# ARP_Odyssey_VCO_1_3.net
KiCad netlist of a schematic drawn in EAGLE
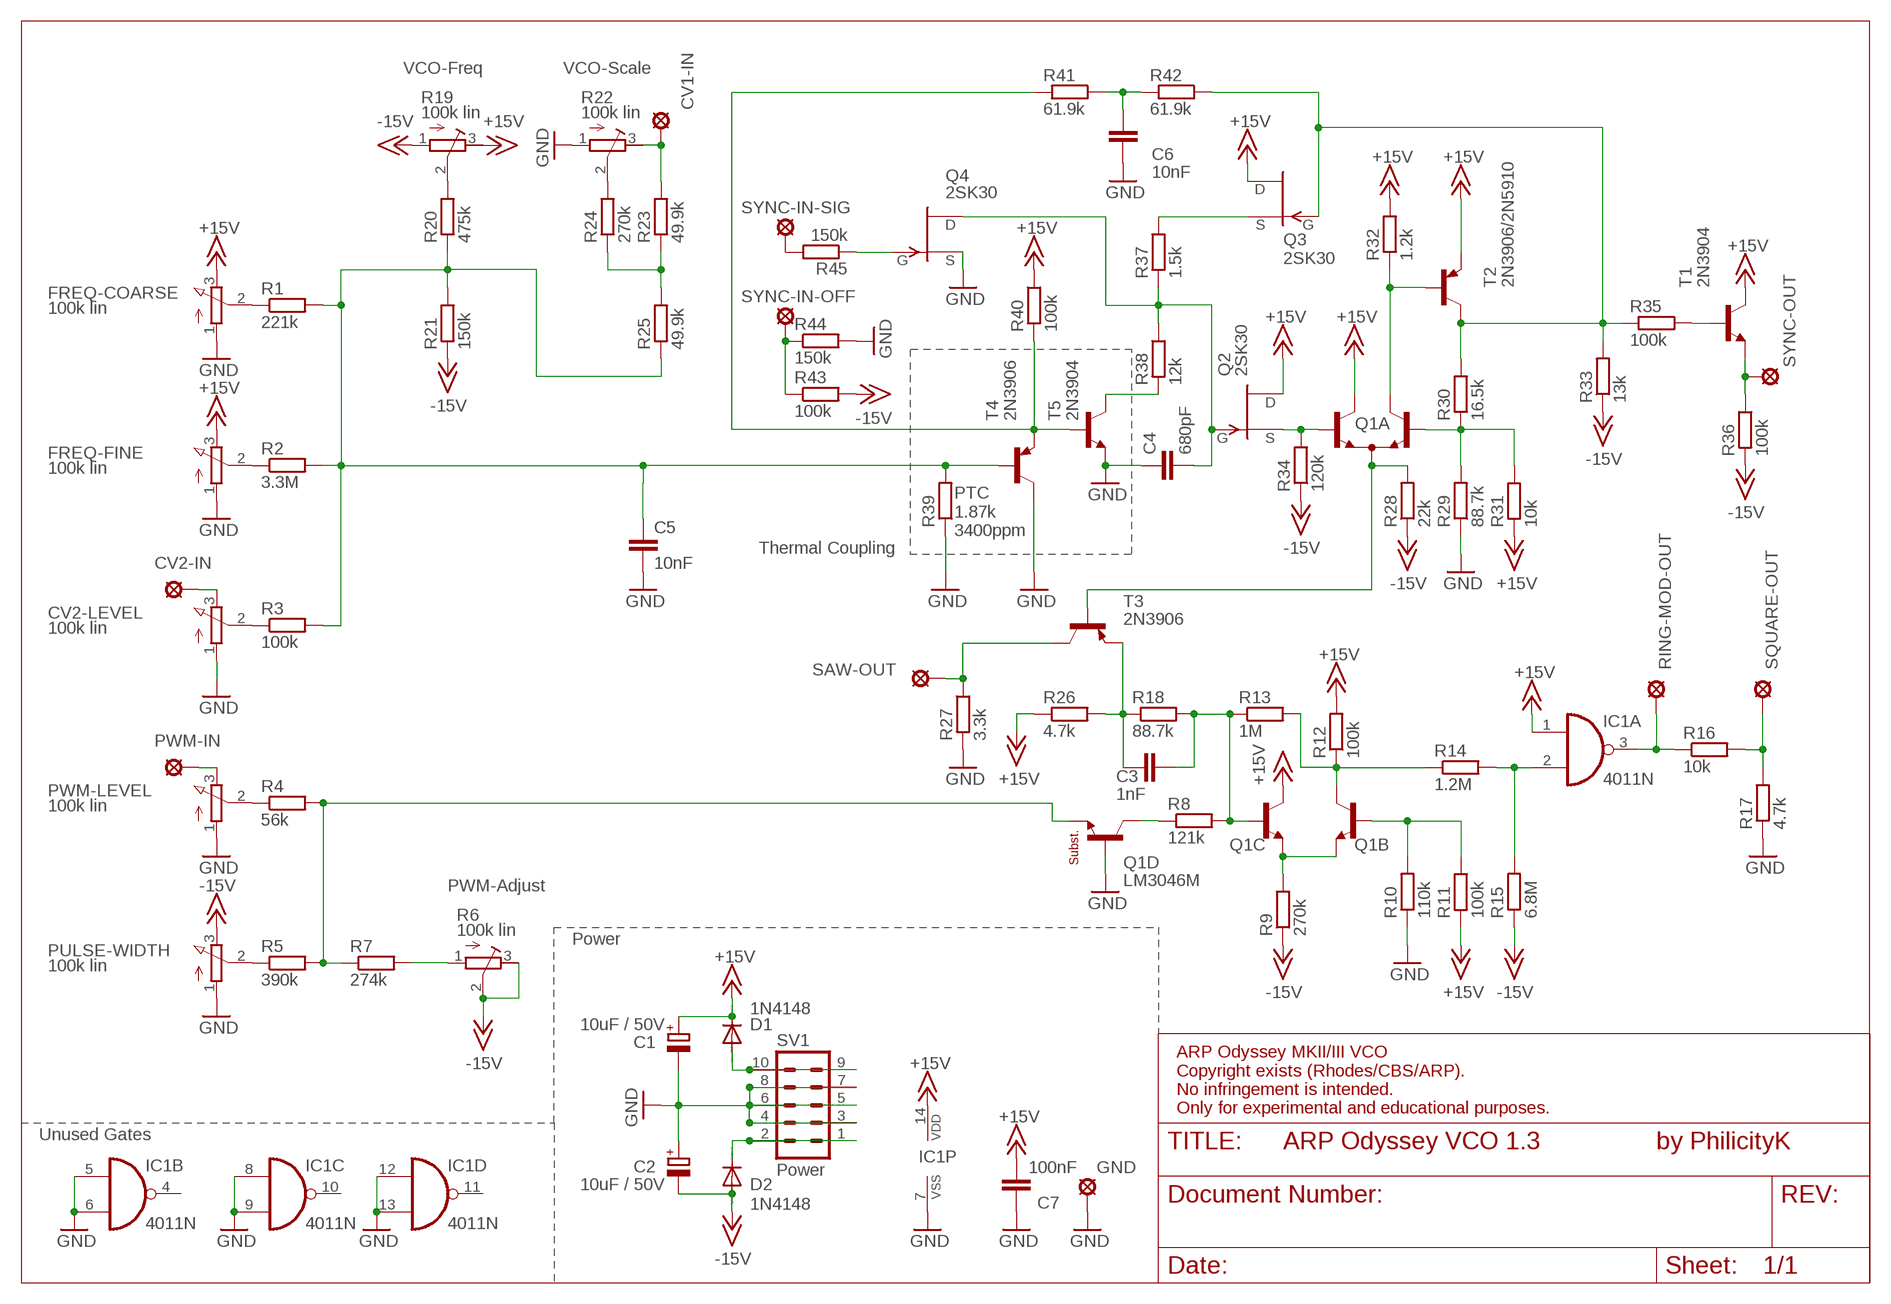
[diagram p0: schematic, sheet 1]

(export (version "E")
  (design (tool "Eeschema 10.0.6"))
  (components
    (comp (ref "C1")
      (value "10uF / 50V")
      (footprint "eagle-import:E2,5-6E")
      (libsource (lib "eagle-import") (part "CPOL-EUE2,5-6E"))
    )
    (comp (ref "C2")
      (value "10uF / 50V")
      (footprint "eagle-import:E2,5-6E")
      (libsource (lib "eagle-import") (part "CPOL-EUE2,5-6E"))
    )
    (comp (ref "C3")
      (value "1nF")
      (footprint "eagle-import:C050-045X075")
      (libsource (lib "eagle-import") (part "C-EU050-045X075"))
    )
    (comp (ref "C4")
      (value "680pF")
      (footprint "eagle-import:C050-045X075")
      (libsource (lib "eagle-import") (part "C-EU050-045X075"))
    )
    (comp (ref "C5")
      (value "10nF")
      (footprint "eagle-import:C050-045X075")
      (libsource (lib "eagle-import") (part "C-EU050-045X075"))
    )
    (comp (ref "C6")
      (value "10nF")
      (footprint "eagle-import:C050-045X075")
      (libsource (lib "eagle-import") (part "C-EU050-045X075"))
    )
    (comp (ref "C7")
      (value "100nF")
      (footprint "eagle-import:C050-045X075")
      (libsource (lib "eagle-import") (part "C-EU050-045X075"))
    )
    (comp (ref "CV1-IN")
      (value "SE11")
      (footprint "eagle-import:SE11")
      (libsource (lib "eagle-import") (part "SE11"))
    )
    (comp (ref "CV2-IN")
      (value "SE11")
      (footprint "eagle-import:SE11")
      (libsource (lib "eagle-import") (part "SE11"))
    )
    (comp (ref "CV2-LEVEL")
      (value "100k lin")
      (footprint "eagle-import:RK11K112")
      (libsource (lib "eagle-import") (part "RK11K112"))
    )
    (comp (ref "D1")
      (value "1N4148")
      (footprint "eagle-import:DO35-7")
      (libsource (lib "eagle-import") (part "1N4148DO35-7"))
    )
    (comp (ref "D2")
      (value "1N4148")
      (footprint "eagle-import:DO35-7")
      (libsource (lib "eagle-import") (part "1N4148DO35-7"))
    )
    (comp (ref "FREQ-COARSE")
      (value "100k lin")
      (footprint "eagle-import:RK11K112")
      (libsource (lib "eagle-import") (part "RK11K112"))
    )
    (comp (ref "FREQ-FINE")
      (value "100k lin")
      (footprint "eagle-import:RK11K112")
      (libsource (lib "eagle-import") (part "RK11K112"))
    )
    (comp (ref "GND")
      (value "SE11")
      (footprint "eagle-import:SE11")
      (libsource (lib "eagle-import") (part "SE11"))
    )
    (comp (ref "IC1")
      (value "4011N")
      (footprint "eagle-import:DIL14")
      (libsource (lib "eagle-import") (part "4011N"))
    )
    (comp (ref "PULSE-WIDTH")
      (value "100k lin")
      (footprint "eagle-import:RK11K112")
      (libsource (lib "eagle-import") (part "RK11K112"))
    )
    (comp (ref "PWM-IN")
      (value "SE11")
      (footprint "eagle-import:SE11")
      (libsource (lib "eagle-import") (part "SE11"))
    )
    (comp (ref "PWM-LEVEL")
      (value "100k lin")
      (footprint "eagle-import:RK11K112")
      (libsource (lib "eagle-import") (part "RK11K112"))
    )
    (comp (ref "Q1")
      (value "LM3046M")
      (footprint "eagle-import:SO14")
      (libsource (lib "eagle-import") (part "LM3046M/NOPB"))
    )
    (comp (ref "Q2")
      (value "2SK30")
      (footprint "eagle-import:TO92")
      (libsource (lib "eagle-import") (part "2SK30"))
    )
    (comp (ref "Q3")
      (value "2SK30")
      (footprint "eagle-import:TO92")
      (libsource (lib "eagle-import") (part "2SK30"))
    )
    (comp (ref "Q4")
      (value "2SK30")
      (footprint "eagle-import:TO92")
      (libsource (lib "eagle-import") (part "2SK30"))
    )
    (comp (ref "R1")
      (value "221k")
      (footprint "eagle-import:0207_7")
      (libsource (lib "eagle-import") (part "R-EU_0207/7"))
    )
    (comp (ref "R2")
      (value "3.3M")
      (footprint "eagle-import:0207_7")
      (libsource (lib "eagle-import") (part "R-EU_0207/7"))
    )
    (comp (ref "R3")
      (value "100k")
      (footprint "eagle-import:0207_7")
      (libsource (lib "eagle-import") (part "R-EU_0207/7"))
    )
    (comp (ref "R4")
      (value "56k")
      (footprint "eagle-import:0207_7")
      (libsource (lib "eagle-import") (part "R-EU_0207/7"))
    )
    (comp (ref "R5")
      (value "390k")
      (footprint "eagle-import:0207_7")
      (libsource (lib "eagle-import") (part "R-EU_0207/7"))
    )
    (comp (ref "R6")
      (value "100k lin")
      (footprint "eagle-import:RTRIM64W")
      (libsource (lib "eagle-import") (part "R-TRIMM64W"))
    )
    (comp (ref "R7")
      (value "274k")
      (footprint "eagle-import:0207_7")
      (libsource (lib "eagle-import") (part "R-EU_0207/7"))
    )
    (comp (ref "R8")
      (value "121k")
      (footprint "eagle-import:0207_7")
      (libsource (lib "eagle-import") (part "R-EU_0207/7"))
    )
    (comp (ref "R9")
      (value "270k")
      (footprint "eagle-import:0207_7")
      (libsource (lib "eagle-import") (part "R-EU_0207/7"))
    )
    (comp (ref "R10")
      (value "110k")
      (footprint "eagle-import:0207_7")
      (libsource (lib "eagle-import") (part "R-EU_0207/7"))
    )
    (comp (ref "R11")
      (value "100k")
      (footprint "eagle-import:0207_7")
      (libsource (lib "eagle-import") (part "R-EU_0207/7"))
    )
    (comp (ref "R12")
      (value "100k")
      (footprint "eagle-import:0207_7")
      (libsource (lib "eagle-import") (part "R-EU_0207/7"))
    )
    (comp (ref "R13")
      (value "1M")
      (footprint "eagle-import:0207_7")
      (libsource (lib "eagle-import") (part "R-EU_0207/7"))
    )
    (comp (ref "R14")
      (value "1.2M")
      (footprint "eagle-import:0207_7")
      (libsource (lib "eagle-import") (part "R-EU_0207/7"))
    )
    (comp (ref "R15")
      (value "6.8M")
      (footprint "eagle-import:0207_7")
      (libsource (lib "eagle-import") (part "R-EU_0207/7"))
    )
    (comp (ref "R16")
      (value "10k")
      (footprint "eagle-import:0207_7")
      (libsource (lib "eagle-import") (part "R-EU_0207/7"))
    )
    (comp (ref "R17")
      (value "4.7k")
      (footprint "eagle-import:0207_7")
      (libsource (lib "eagle-import") (part "R-EU_0207/7"))
    )
    (comp (ref "R18")
      (value "88.7k")
      (footprint "eagle-import:0207_7")
      (libsource (lib "eagle-import") (part "R-EU_0207/7"))
    )
    (comp (ref "R19")
      (value "100k lin")
      (footprint "eagle-import:RTRIM64W")
      (libsource (lib "eagle-import") (part "R-TRIMM64W"))
    )
    (comp (ref "R20")
      (value "475k")
      (footprint "eagle-import:0207_7")
      (libsource (lib "eagle-import") (part "R-EU_0207/7"))
    )
    (comp (ref "R21")
      (value "150k")
      (footprint "eagle-import:0207_7")
      (libsource (lib "eagle-import") (part "R-EU_0207/7"))
    )
    (comp (ref "R22")
      (value "100k lin")
      (footprint "eagle-import:RTRIM64W")
      (libsource (lib "eagle-import") (part "R-TRIMM64W"))
    )
    (comp (ref "R23")
      (value "49.9k")
      (footprint "eagle-import:0207_7")
      (libsource (lib "eagle-import") (part "R-EU_0207/7"))
    )
    (comp (ref "R24")
      (value "270k")
      (footprint "eagle-import:0207_7")
      (libsource (lib "eagle-import") (part "R-EU_0207/7"))
    )
    (comp (ref "R25")
      (value "49.9k")
      (footprint "eagle-import:0207_7")
      (libsource (lib "eagle-import") (part "R-EU_0207/7"))
    )
    (comp (ref "R26")
      (value "4.7k")
      (footprint "eagle-import:0207_7")
      (libsource (lib "eagle-import") (part "R-EU_0207/7"))
    )
    (comp (ref "R27")
      (value "3.3k")
      (footprint "eagle-import:0207_7")
      (libsource (lib "eagle-import") (part "R-EU_0207/7"))
    )
    (comp (ref "R28")
      (value "22k")
      (footprint "eagle-import:0207_7")
      (libsource (lib "eagle-import") (part "R-EU_0207/7"))
    )
    (comp (ref "R29")
      (value "88.7k")
      (footprint "eagle-import:0207_7")
      (libsource (lib "eagle-import") (part "R-EU_0207/7"))
    )
    (comp (ref "R30")
      (value "16.5k")
      (footprint "eagle-import:0207_7")
      (libsource (lib "eagle-import") (part "R-EU_0207/7"))
    )
    (comp (ref "R31")
      (value "10k")
      (footprint "eagle-import:0207_7")
      (libsource (lib "eagle-import") (part "R-EU_0207/7"))
    )
    (comp (ref "R32")
      (value "1.2k")
      (footprint "eagle-import:0207_7")
      (libsource (lib "eagle-import") (part "R-EU_0207/7"))
    )
    (comp (ref "R33")
      (value "13k")
      (footprint "eagle-import:0207_7")
      (libsource (lib "eagle-import") (part "R-EU_0207/7"))
    )
    (comp (ref "R34")
      (value "120k")
      (footprint "eagle-import:0207_7")
      (libsource (lib "eagle-import") (part "R-EU_0207/7"))
    )
    (comp (ref "R35")
      (value "100k")
      (footprint "eagle-import:0207_7")
      (libsource (lib "eagle-import") (part "R-EU_0207/7"))
    )
    (comp (ref "R36")
      (value "100k")
      (footprint "eagle-import:0207_7")
      (libsource (lib "eagle-import") (part "R-EU_0207/7"))
    )
    (comp (ref "R37")
      (value "1.5k")
      (footprint "eagle-import:0207_7")
      (libsource (lib "eagle-import") (part "R-EU_0207/7"))
    )
    (comp (ref "R38")
      (value "12k")
      (footprint "eagle-import:0207_7")
      (libsource (lib "eagle-import") (part "R-EU_0207/7"))
    )
    (comp (ref "R39")
      (value "PTC 1.87k")
      (footprint "eagle-import:0207_7")
      (libsource (lib "eagle-import") (part "R-EU_0207/7"))
    )
    (comp (ref "R40")
      (value "100k")
      (footprint "eagle-import:0207_7")
      (libsource (lib "eagle-import") (part "R-EU_0207/7"))
    )
    (comp (ref "R41")
      (value "61.9k")
      (footprint "eagle-import:0207_7")
      (libsource (lib "eagle-import") (part "R-EU_0207/7"))
    )
    (comp (ref "R42")
      (value "61.9k")
      (footprint "eagle-import:0207_7")
      (libsource (lib "eagle-import") (part "R-EU_0207/7"))
    )
    (comp (ref "R43")
      (value "100k")
      (footprint "eagle-import:0207_7")
      (libsource (lib "eagle-import") (part "R-EU_0207/7"))
    )
    (comp (ref "R44")
      (value "150k")
      (footprint "eagle-import:0207_7")
      (libsource (lib "eagle-import") (part "R-EU_0207/7"))
    )
    (comp (ref "R45")
      (value "150k")
      (footprint "eagle-import:0207_7")
      (libsource (lib "eagle-import") (part "R-EU_0207/7"))
    )
    (comp (ref "RING-MOD-OUT")
      (value "SE11")
      (footprint "eagle-import:SE11")
      (libsource (lib "eagle-import") (part "SE11"))
    )
    (comp (ref "SAW-OUT")
      (value "SE11")
      (footprint "eagle-import:SE11")
      (libsource (lib "eagle-import") (part "SE11"))
    )
    (comp (ref "SQUARE-OUT")
      (value "SE11")
      (footprint "eagle-import:SE11")
      (libsource (lib "eagle-import") (part "SE11"))
    )
    (comp (ref "SV1")
      (value "Power")
      (footprint "eagle-import:ML10")
      (libsource (lib "eagle-import") (part "ML10"))
    )
    (comp (ref "SYNC-IN-OFF")
      (value "SE11")
      (footprint "eagle-import:SE11")
      (libsource (lib "eagle-import") (part "SE11"))
    )
    (comp (ref "SYNC-IN-SIG")
      (value "SE11")
      (footprint "eagle-import:SE11")
      (libsource (lib "eagle-import") (part "SE11"))
    )
    (comp (ref "SYNC-OUT")
      (value "SE11")
      (footprint "eagle-import:SE11")
      (libsource (lib "eagle-import") (part "SE11"))
    )
    (comp (ref "T1")
      (value "2N3904")
      (footprint "eagle-import:TO92-EBC")
      (libsource (lib "eagle-import") (part "-NPN-TO92-EBC2N3904"))
    )
    (comp (ref "T2")
      (value "2N3906/2N5910")
      (footprint "eagle-import:TO92-EBC")
      (libsource (lib "eagle-import") (part "-PNP-TO92-EBC2N3906"))
    )
    (comp (ref "T3")
      (value "2N3906")
      (footprint "eagle-import:TO92-EBC")
      (libsource (lib "eagle-import") (part "-PNP-TO92-EBC2N3906"))
    )
    (comp (ref "T4")
      (value "2N3906")
      (footprint "eagle-import:TO92-EBC")
      (libsource (lib "eagle-import") (part "-PNP-TO92-EBC2N3906"))
    )
    (comp (ref "T5")
      (value "2N3904")
      (footprint "eagle-import:TO92-EBC")
      (libsource (lib "eagle-import") (part "-NPN-TO92-EBC2N3904"))
    )
  )
  (nets
    (net (code "1") (name "+15V") (class "Default")
      (node (ref "C1") (pin "+") (pinfunction "+_+") (pintype "passive"))
      (node (ref "C7") (pin "2") (pinfunction "2_2") (pintype "passive"))
      (node (ref "D1") (pin "C") (pinfunction "C_C") (pintype "passive"))
      (node (ref "FREQ-COARSE") (pin "3") (pinfunction "E_3") (pintype "passive"))
      (node (ref "FREQ-FINE") (pin "3") (pinfunction "E_3") (pintype "passive"))
      (node (ref "IC1") (pin "1") (pinfunction "I0_1") (pintype "input"))
      (node (ref "IC1") (pin "14") (pinfunction "VDD_14") (pintype "power_in"))
      (node (ref "Q1") (pin "11") (pinfunction "C_11") (pintype "passive"))
      (node (ref "Q1") (pin "5") (pinfunction "C2_5") (pintype "passive"))
      (node (ref "Q2") (pin "3") (pinfunction "D_3") (pintype "passive"))
      (node (ref "Q3") (pin "3") (pinfunction "D_3") (pintype "passive"))
      (node (ref "R11") (pin "2") (pinfunction "2_2") (pintype "passive"))
      (node (ref "R12") (pin "2") (pinfunction "2_2") (pintype "passive"))
      (node (ref "R19") (pin "3") (pinfunction "E_3") (pintype "passive"))
      (node (ref "R26") (pin "1") (pinfunction "1_1") (pintype "passive"))
      (node (ref "R31") (pin "2") (pinfunction "2_2") (pintype "passive"))
      (node (ref "R32") (pin "2") (pinfunction "2_2") (pintype "passive"))
      (node (ref "R40") (pin "1") (pinfunction "1_1") (pintype "passive"))
      (node (ref "T1") (pin "C") (pinfunction "C_C") (pintype "passive"))
      (node (ref "T2") (pin "E") (pinfunction "E_E") (pintype "passive"))
    )
    (net (code "2") (name "-15V") (class "Default")
      (node (ref "C2") (pin "-") (pinfunction "-_-") (pintype "passive"))
      (node (ref "D2") (pin "A") (pinfunction "A_A") (pintype "passive"))
      (node (ref "PULSE-WIDTH") (pin "3") (pinfunction "E_3") (pintype "passive"))
      (node (ref "R15") (pin "1") (pinfunction "1_1") (pintype "passive"))
      (node (ref "R19") (pin "1") (pinfunction "A_1") (pintype "passive"))
      (node (ref "R21") (pin "2") (pinfunction "2_2") (pintype "passive"))
      (node (ref "R28") (pin "1") (pinfunction "1_1") (pintype "passive"))
      (node (ref "R33") (pin "1") (pinfunction "1_1") (pintype "passive"))
      (node (ref "R34") (pin "1") (pinfunction "1_1") (pintype "passive"))
      (node (ref "R36") (pin "2") (pinfunction "2_2") (pintype "passive"))
      (node (ref "R43") (pin "2") (pinfunction "2_2") (pintype "passive"))
      (node (ref "R6") (pin "2") (pinfunction "S_2") (pintype "passive"))
      (node (ref "R6") (pin "3") (pinfunction "E_3") (pintype "passive"))
      (node (ref "R9") (pin "1") (pinfunction "1_1") (pintype "passive"))
    )
    (net (code "3") (name "GND") (class "Default")
      (node (ref "C1") (pin "-") (pinfunction "-_-") (pintype "passive"))
      (node (ref "C2") (pin "+") (pinfunction "+_+") (pintype "passive"))
      (node (ref "C4") (pin "1") (pinfunction "1_1") (pintype "passive"))
      (node (ref "C5") (pin "2") (pinfunction "2_2") (pintype "passive"))
      (node (ref "C6") (pin "2") (pinfunction "2_2") (pintype "passive"))
      (node (ref "C7") (pin "1") (pinfunction "1_1") (pintype "passive"))
      (node (ref "CV2-LEVEL") (pin "1") (pinfunction "A_1") (pintype "passive"))
      (node (ref "FREQ-COARSE") (pin "1") (pinfunction "A_1") (pintype "passive"))
      (node (ref "FREQ-FINE") (pin "1") (pinfunction "A_1") (pintype "passive"))
      (node (ref "GND") (pin "MP") (pinfunction "MP_MP") (pintype "passive"))
      (node (ref "IC1") (pin "12") (pinfunction "I0_12") (pintype "input"))
      (node (ref "IC1") (pin "13") (pinfunction "I1_13") (pintype "input"))
      (node (ref "IC1") (pin "5") (pinfunction "I0_5") (pintype "input"))
      (node (ref "IC1") (pin "6") (pinfunction "I1_6") (pintype "input"))
      (node (ref "IC1") (pin "7") (pinfunction "VSS_7") (pintype "power_in"))
      (node (ref "IC1") (pin "8") (pinfunction "I0_8") (pintype "input"))
      (node (ref "IC1") (pin "9") (pinfunction "I1_9") (pintype "input"))
      (node (ref "PULSE-WIDTH") (pin "1") (pinfunction "A_1") (pintype "passive"))
      (node (ref "PWM-LEVEL") (pin "1") (pinfunction "A_1") (pintype "passive"))
      (node (ref "Q1") (pin "12") (pinfunction "B_12") (pintype "passive"))
      (node (ref "Q4") (pin "1") (pinfunction "S_1") (pintype "passive"))
      (node (ref "R10") (pin "1") (pinfunction "1_1") (pintype "passive"))
      (node (ref "R17") (pin "1") (pinfunction "1_1") (pintype "passive"))
      (node (ref "R22") (pin "1") (pinfunction "A_1") (pintype "passive"))
      (node (ref "R27") (pin "2") (pinfunction "2_2") (pintype "passive"))
      (node (ref "R29") (pin "1") (pinfunction "1_1") (pintype "passive"))
      (node (ref "R39") (pin "1") (pinfunction "1_1") (pintype "passive"))
      (node (ref "R44") (pin "2") (pinfunction "2_2") (pintype "passive"))
      (node (ref "SV1") (pin "3") (pinfunction "3_3") (pintype "passive"))
      (node (ref "SV1") (pin "4") (pinfunction "4_4") (pintype "passive"))
      (node (ref "SV1") (pin "5") (pinfunction "5_5") (pintype "passive"))
      (node (ref "SV1") (pin "6") (pinfunction "6_6") (pintype "passive"))
      (node (ref "SV1") (pin "7") (pinfunction "7_7") (pintype "passive"))
      (node (ref "SV1") (pin "8") (pinfunction "8_8") (pintype "passive"))
      (node (ref "T4") (pin "C") (pinfunction "C_C") (pintype "passive"))
      (node (ref "T5") (pin "E") (pinfunction "E_E") (pintype "passive"))
    )
    (net (code "4") (name "Net-(C3-Pad1)") (class "Default")
      (node (ref "C3") (pin "1") (pinfunction "1_1") (pintype "passive"))
      (node (ref "R18") (pin "1") (pinfunction "1_1") (pintype "passive"))
      (node (ref "R26") (pin "2") (pinfunction "2_2") (pintype "passive"))
      (node (ref "T3") (pin "E") (pinfunction "E_E") (pintype "passive"))
    )
    (net (code "5") (name "Net-(C5-Pad1)") (class "Default")
      (node (ref "C5") (pin "1") (pinfunction "1_1") (pintype "passive"))
      (node (ref "R1") (pin "2") (pinfunction "2_2") (pintype "passive"))
      (node (ref "R2") (pin "2") (pinfunction "2_2") (pintype "passive"))
      (node (ref "R20") (pin "2") (pinfunction "2_2") (pintype "passive"))
      (node (ref "R21") (pin "1") (pinfunction "1_1") (pintype "passive"))
      (node (ref "R25") (pin "2") (pinfunction "2_2") (pintype "passive"))
      (node (ref "R3") (pin "2") (pinfunction "2_2") (pintype "passive"))
      (node (ref "R39") (pin "2") (pinfunction "2_2") (pintype "passive"))
      (node (ref "T4") (pin "B") (pinfunction "B_B") (pintype "passive"))
    )
    (net (code "6") (name "Net-(C6-Pad1)") (class "Default")
      (node (ref "C6") (pin "1") (pinfunction "1_1") (pintype "passive"))
      (node (ref "R41") (pin "1") (pinfunction "1_1") (pintype "passive"))
      (node (ref "R42") (pin "2") (pinfunction "2_2") (pintype "passive"))
    )
    (net (code "7") (name "Net-(CV2-LEVEL-E)") (class "Default")
      (node (ref "CV2-IN") (pin "MP") (pinfunction "MP_MP") (pintype "passive"))
      (node (ref "CV2-LEVEL") (pin "3") (pinfunction "E_3") (pintype "passive"))
    )
    (net (code "8") (name "Net-(CV2-LEVEL-S)") (class "Default")
      (node (ref "CV2-LEVEL") (pin "2") (pinfunction "S_2") (pintype "passive"))
      (node (ref "R3") (pin "1") (pinfunction "1_1") (pintype "passive"))
    )
    (net (code "9") (name "Net-(D1-PadA)") (class "Default")
      (node (ref "D1") (pin "A") (pinfunction "A_A") (pintype "passive"))
      (node (ref "SV1") (pin "10") (pinfunction "10_10") (pintype "passive"))
      (node (ref "SV1") (pin "9") (pinfunction "9_9") (pintype "passive"))
    )
    (net (code "10") (name "Net-(D2-PadC)") (class "Default")
      (node (ref "D2") (pin "C") (pinfunction "C_C") (pintype "passive"))
      (node (ref "SV1") (pin "1") (pinfunction "1_1") (pintype "passive"))
      (node (ref "SV1") (pin "2") (pinfunction "2_2") (pintype "passive"))
    )
    (net (code "11") (name "Net-(FREQ-COARSE-S)") (class "Default")
      (node (ref "FREQ-COARSE") (pin "2") (pinfunction "S_2") (pintype "passive"))
      (node (ref "R1") (pin "1") (pinfunction "1_1") (pintype "passive"))
    )
    (net (code "12") (name "Net-(FREQ-FINE-S)") (class "Default")
      (node (ref "FREQ-FINE") (pin "2") (pinfunction "S_2") (pintype "passive"))
      (node (ref "R2") (pin "1") (pinfunction "1_1") (pintype "passive"))
    )
    (net (code "13") (name "Net-(IC1A-I1)") (class "Default")
      (node (ref "IC1") (pin "2") (pinfunction "I1_2") (pintype "input"))
      (node (ref "R14") (pin "2") (pinfunction "2_2") (pintype "passive"))
      (node (ref "R15") (pin "2") (pinfunction "2_2") (pintype "passive"))
    )
    (net (code "14") (name "Net-(IC1A-O)") (class "Default")
      (node (ref "IC1") (pin "3") (pinfunction "O_3") (pintype "output"))
      (node (ref "R16") (pin "1") (pinfunction "1_1") (pintype "passive"))
      (node (ref "RING-MOD-OUT") (pin "MP") (pinfunction "MP_MP") (pintype "passive"))
    )
    (net (code "15") (name "Net-(PULSE-WIDTH-S)") (class "Default")
      (node (ref "PULSE-WIDTH") (pin "2") (pinfunction "S_2") (pintype "passive"))
      (node (ref "R5") (pin "1") (pinfunction "1_1") (pintype "passive"))
    )
    (net (code "16") (name "Net-(PWM-LEVEL-E)") (class "Default")
      (node (ref "PWM-IN") (pin "MP") (pinfunction "MP_MP") (pintype "passive"))
      (node (ref "PWM-LEVEL") (pin "3") (pinfunction "E_3") (pintype "passive"))
    )
    (net (code "17") (name "Net-(PWM-LEVEL-S)") (class "Default")
      (node (ref "PWM-LEVEL") (pin "2") (pinfunction "S_2") (pintype "passive"))
      (node (ref "R4") (pin "1") (pinfunction "1_1") (pintype "passive"))
    )
    (net (code "18") (name "Net-(Q1A-B1)") (class "Default")
      (node (ref "Q1") (pin "2") (pinfunction "B1_2") (pintype "passive"))
      (node (ref "R29") (pin "2") (pinfunction "2_2") (pintype "passive"))
      (node (ref "R30") (pin "1") (pinfunction "1_1") (pintype "passive"))
      (node (ref "R31") (pin "1") (pinfunction "1_1") (pintype "passive"))
    )
    (net (code "19") (name "Net-(Q1A-B2)") (class "Default")
      (node (ref "Q1") (pin "4") (pinfunction "B2_4") (pintype "passive"))
      (node (ref "Q2") (pin "1") (pinfunction "S_1") (pintype "passive"))
      (node (ref "R34") (pin "2") (pinfunction "2_2") (pintype "passive"))
    )
    (net (code "20") (name "Net-(Q1A-C1)") (class "Default")
      (node (ref "Q1") (pin "1") (pinfunction "C1_1") (pintype "passive"))
      (node (ref "R32") (pin "1") (pinfunction "1_1") (pintype "passive"))
      (node (ref "T2") (pin "B") (pinfunction "B_B") (pintype "passive"))
    )
    (net (code "21") (name "Net-(Q1A-E)") (class "Default")
      (node (ref "Q1") (pin "3") (pinfunction "E_3") (pintype "passive"))
      (node (ref "R28") (pin "2") (pinfunction "2_2") (pintype "passive"))
      (node (ref "T3") (pin "B") (pinfunction "B_B") (pintype "passive"))
    )
    (net (code "22") (name "Net-(Q1B-B)") (class "Default")
      (node (ref "Q1") (pin "6") (pinfunction "B_6") (pintype "passive"))
      (node (ref "R10") (pin "2") (pinfunction "2_2") (pintype "passive"))
      (node (ref "R11") (pin "1") (pinfunction "1_1") (pintype "passive"))
    )
    (net (code "23") (name "Net-(Q1B-C)") (class "Default")
      (node (ref "Q1") (pin "8") (pinfunction "C_8") (pintype "passive"))
      (node (ref "R12") (pin "1") (pinfunction "1_1") (pintype "passive"))
      (node (ref "R13") (pin "2") (pinfunction "2_2") (pintype "passive"))
      (node (ref "R14") (pin "1") (pinfunction "1_1") (pintype "passive"))
    )
    (net (code "24") (name "Net-(Q1B-E)") (class "Default")
      (node (ref "Q1") (pin "10") (pinfunction "E_10") (pintype "passive"))
      (node (ref "Q1") (pin "7") (pinfunction "E_7") (pintype "passive"))
      (node (ref "R9") (pin "2") (pinfunction "2_2") (pintype "passive"))
    )
    (net (code "25") (name "Net-(Q1C-B)") (class "Default")
      (node (ref "C3") (pin "2") (pinfunction "2_2") (pintype "passive"))
      (node (ref "Q1") (pin "9") (pinfunction "B_9") (pintype "passive"))
      (node (ref "R13") (pin "1") (pinfunction "1_1") (pintype "passive"))
      (node (ref "R18") (pin "2") (pinfunction "2_2") (pintype "passive"))
      (node (ref "R8") (pin "2") (pinfunction "2_2") (pintype "passive"))
    )
    (net (code "26") (name "Net-(Q1D-C)") (class "Default")
      (node (ref "Q1") (pin "14") (pinfunction "C_14") (pintype "passive"))
      (node (ref "R8") (pin "1") (pinfunction "1_1") (pintype "passive"))
    )
    (net (code "27") (name "Net-(Q1D-E)") (class "Default")
      (node (ref "Q1") (pin "13") (pinfunction "E_13") (pintype "passive"))
      (node (ref "R4") (pin "2") (pinfunction "2_2") (pintype "passive"))
      (node (ref "R5") (pin "2") (pinfunction "2_2") (pintype "passive"))
      (node (ref "R7") (pin "1") (pinfunction "1_1") (pintype "passive"))
    )
    (net (code "28") (name "Net-(Q2-G)") (class "Default")
      (node (ref "C4") (pin "2") (pinfunction "2_2") (pintype "passive"))
      (node (ref "Q2") (pin "2") (pinfunction "G_2") (pintype "passive"))
      (node (ref "Q4") (pin "3") (pinfunction "D_3") (pintype "passive"))
      (node (ref "R37") (pin "2") (pinfunction "2_2") (pintype "passive"))
      (node (ref "R38") (pin "1") (pinfunction "1_1") (pintype "passive"))
    )
    (net (code "29") (name "Net-(Q3-G)") (class "Default")
      (node (ref "Q3") (pin "2") (pinfunction "G_2") (pintype "passive"))
      (node (ref "R30") (pin "2") (pinfunction "2_2") (pintype "passive"))
      (node (ref "R33") (pin "2") (pinfunction "2_2") (pintype "passive"))
      (node (ref "R35") (pin "2") (pinfunction "2_2") (pintype "passive"))
      (node (ref "R42") (pin "1") (pinfunction "1_1") (pintype "passive"))
      (node (ref "T2") (pin "C") (pinfunction "C_C") (pintype "passive"))
    )
    (net (code "30") (name "Net-(Q3-S)") (class "Default")
      (node (ref "Q3") (pin "1") (pinfunction "S_1") (pintype "passive"))
      (node (ref "R37") (pin "1") (pinfunction "1_1") (pintype "passive"))
    )
    (net (code "31") (name "Net-(Q4-G)") (class "Default")
      (node (ref "Q4") (pin "2") (pinfunction "G_2") (pintype "passive"))
      (node (ref "R45") (pin "1") (pinfunction "1_1") (pintype "passive"))
    )
    (net (code "32") (name "Net-(R6-A)") (class "Default")
      (node (ref "R6") (pin "1") (pinfunction "A_1") (pintype "passive"))
      (node (ref "R7") (pin "2") (pinfunction "2_2") (pintype "passive"))
    )
    (net (code "33") (name "Net-(R16-Pad2)") (class "Default")
      (node (ref "R16") (pin "2") (pinfunction "2_2") (pintype "passive"))
      (node (ref "R17") (pin "2") (pinfunction "2_2") (pintype "passive"))
      (node (ref "SQUARE-OUT") (pin "MP") (pinfunction "MP_MP") (pintype "passive"))
    )
    (net (code "34") (name "Net-(R19-S)") (class "Default")
      (node (ref "R19") (pin "2") (pinfunction "S_2") (pintype "passive"))
      (node (ref "R20") (pin "1") (pinfunction "1_1") (pintype "passive"))
    )
    (net (code "35") (name "Net-(R22-E)") (class "Default")
      (node (ref "CV1-IN") (pin "MP") (pinfunction "MP_MP") (pintype "passive"))
      (node (ref "R22") (pin "3") (pinfunction "E_3") (pintype "passive"))
      (node (ref "R23") (pin "1") (pinfunction "1_1") (pintype "passive"))
    )
    (net (code "36") (name "Net-(R22-S)") (class "Default")
      (node (ref "R22") (pin "2") (pinfunction "S_2") (pintype "passive"))
      (node (ref "R24") (pin "1") (pinfunction "1_1") (pintype "passive"))
    )
    (net (code "37") (name "Net-(R23-Pad2)") (class "Default")
      (node (ref "R23") (pin "2") (pinfunction "2_2") (pintype "passive"))
      (node (ref "R24") (pin "2") (pinfunction "2_2") (pintype "passive"))
      (node (ref "R25") (pin "1") (pinfunction "1_1") (pintype "passive"))
    )
    (net (code "38") (name "Net-(R27-Pad1)") (class "Default")
      (node (ref "R27") (pin "1") (pinfunction "1_1") (pintype "passive"))
      (node (ref "SAW-OUT") (pin "MP") (pinfunction "MP_MP") (pintype "passive"))
      (node (ref "T3") (pin "C") (pinfunction "C_C") (pintype "passive"))
    )
    (net (code "39") (name "Net-(R35-Pad1)") (class "Default")
      (node (ref "R35") (pin "1") (pinfunction "1_1") (pintype "passive"))
      (node (ref "T1") (pin "B") (pinfunction "B_B") (pintype "passive"))
    )
    (net (code "40") (name "Net-(R36-Pad1)") (class "Default")
      (node (ref "R36") (pin "1") (pinfunction "1_1") (pintype "passive"))
      (node (ref "SYNC-OUT") (pin "MP") (pinfunction "MP_MP") (pintype "passive"))
      (node (ref "T1") (pin "E") (pinfunction "E_E") (pintype "passive"))
    )
    (net (code "41") (name "Net-(R38-Pad2)") (class "Default")
      (node (ref "R38") (pin "2") (pinfunction "2_2") (pintype "passive"))
      (node (ref "T5") (pin "C") (pinfunction "C_C") (pintype "passive"))
    )
    (net (code "42") (name "Net-(R40-Pad2)") (class "Default")
      (node (ref "R40") (pin "2") (pinfunction "2_2") (pintype "passive"))
      (node (ref "R41") (pin "2") (pinfunction "2_2") (pintype "passive"))
      (node (ref "T4") (pin "E") (pinfunction "E_E") (pintype "passive"))
      (node (ref "T5") (pin "B") (pinfunction "B_B") (pintype "passive"))
    )
    (net (code "43") (name "Net-(R43-Pad1)") (class "Default")
      (node (ref "R43") (pin "1") (pinfunction "1_1") (pintype "passive"))
      (node (ref "R44") (pin "1") (pinfunction "1_1") (pintype "passive"))
      (node (ref "SYNC-IN-OFF") (pin "MP") (pinfunction "MP_MP") (pintype "passive"))
    )
    (net (code "44") (name "Net-(R45-Pad2)") (class "Default")
      (node (ref "R45") (pin "2") (pinfunction "2_2") (pintype "passive"))
      (node (ref "SYNC-IN-SIG") (pin "MP") (pinfunction "MP_MP") (pintype "passive"))
    )
    (net (code "45") (name "unconnected-(IC1B-O-Pad4)") (class "Default")
      (node (ref "IC1") (pin "4") (pinfunction "O_4") (pintype "output"))
    )
    (net (code "46") (name "unconnected-(IC1C-O-Pad10)") (class "Default")
      (node (ref "IC1") (pin "10") (pinfunction "O_10") (pintype "output"))
    )
    (net (code "47") (name "unconnected-(IC1D-O-Pad11)") (class "Default")
      (node (ref "IC1") (pin "11") (pinfunction "O_11") (pintype "output"))
    )
  )
)
